# OpampTestBoard.net
KiCad netlist of a schematic drawn in EAGLE
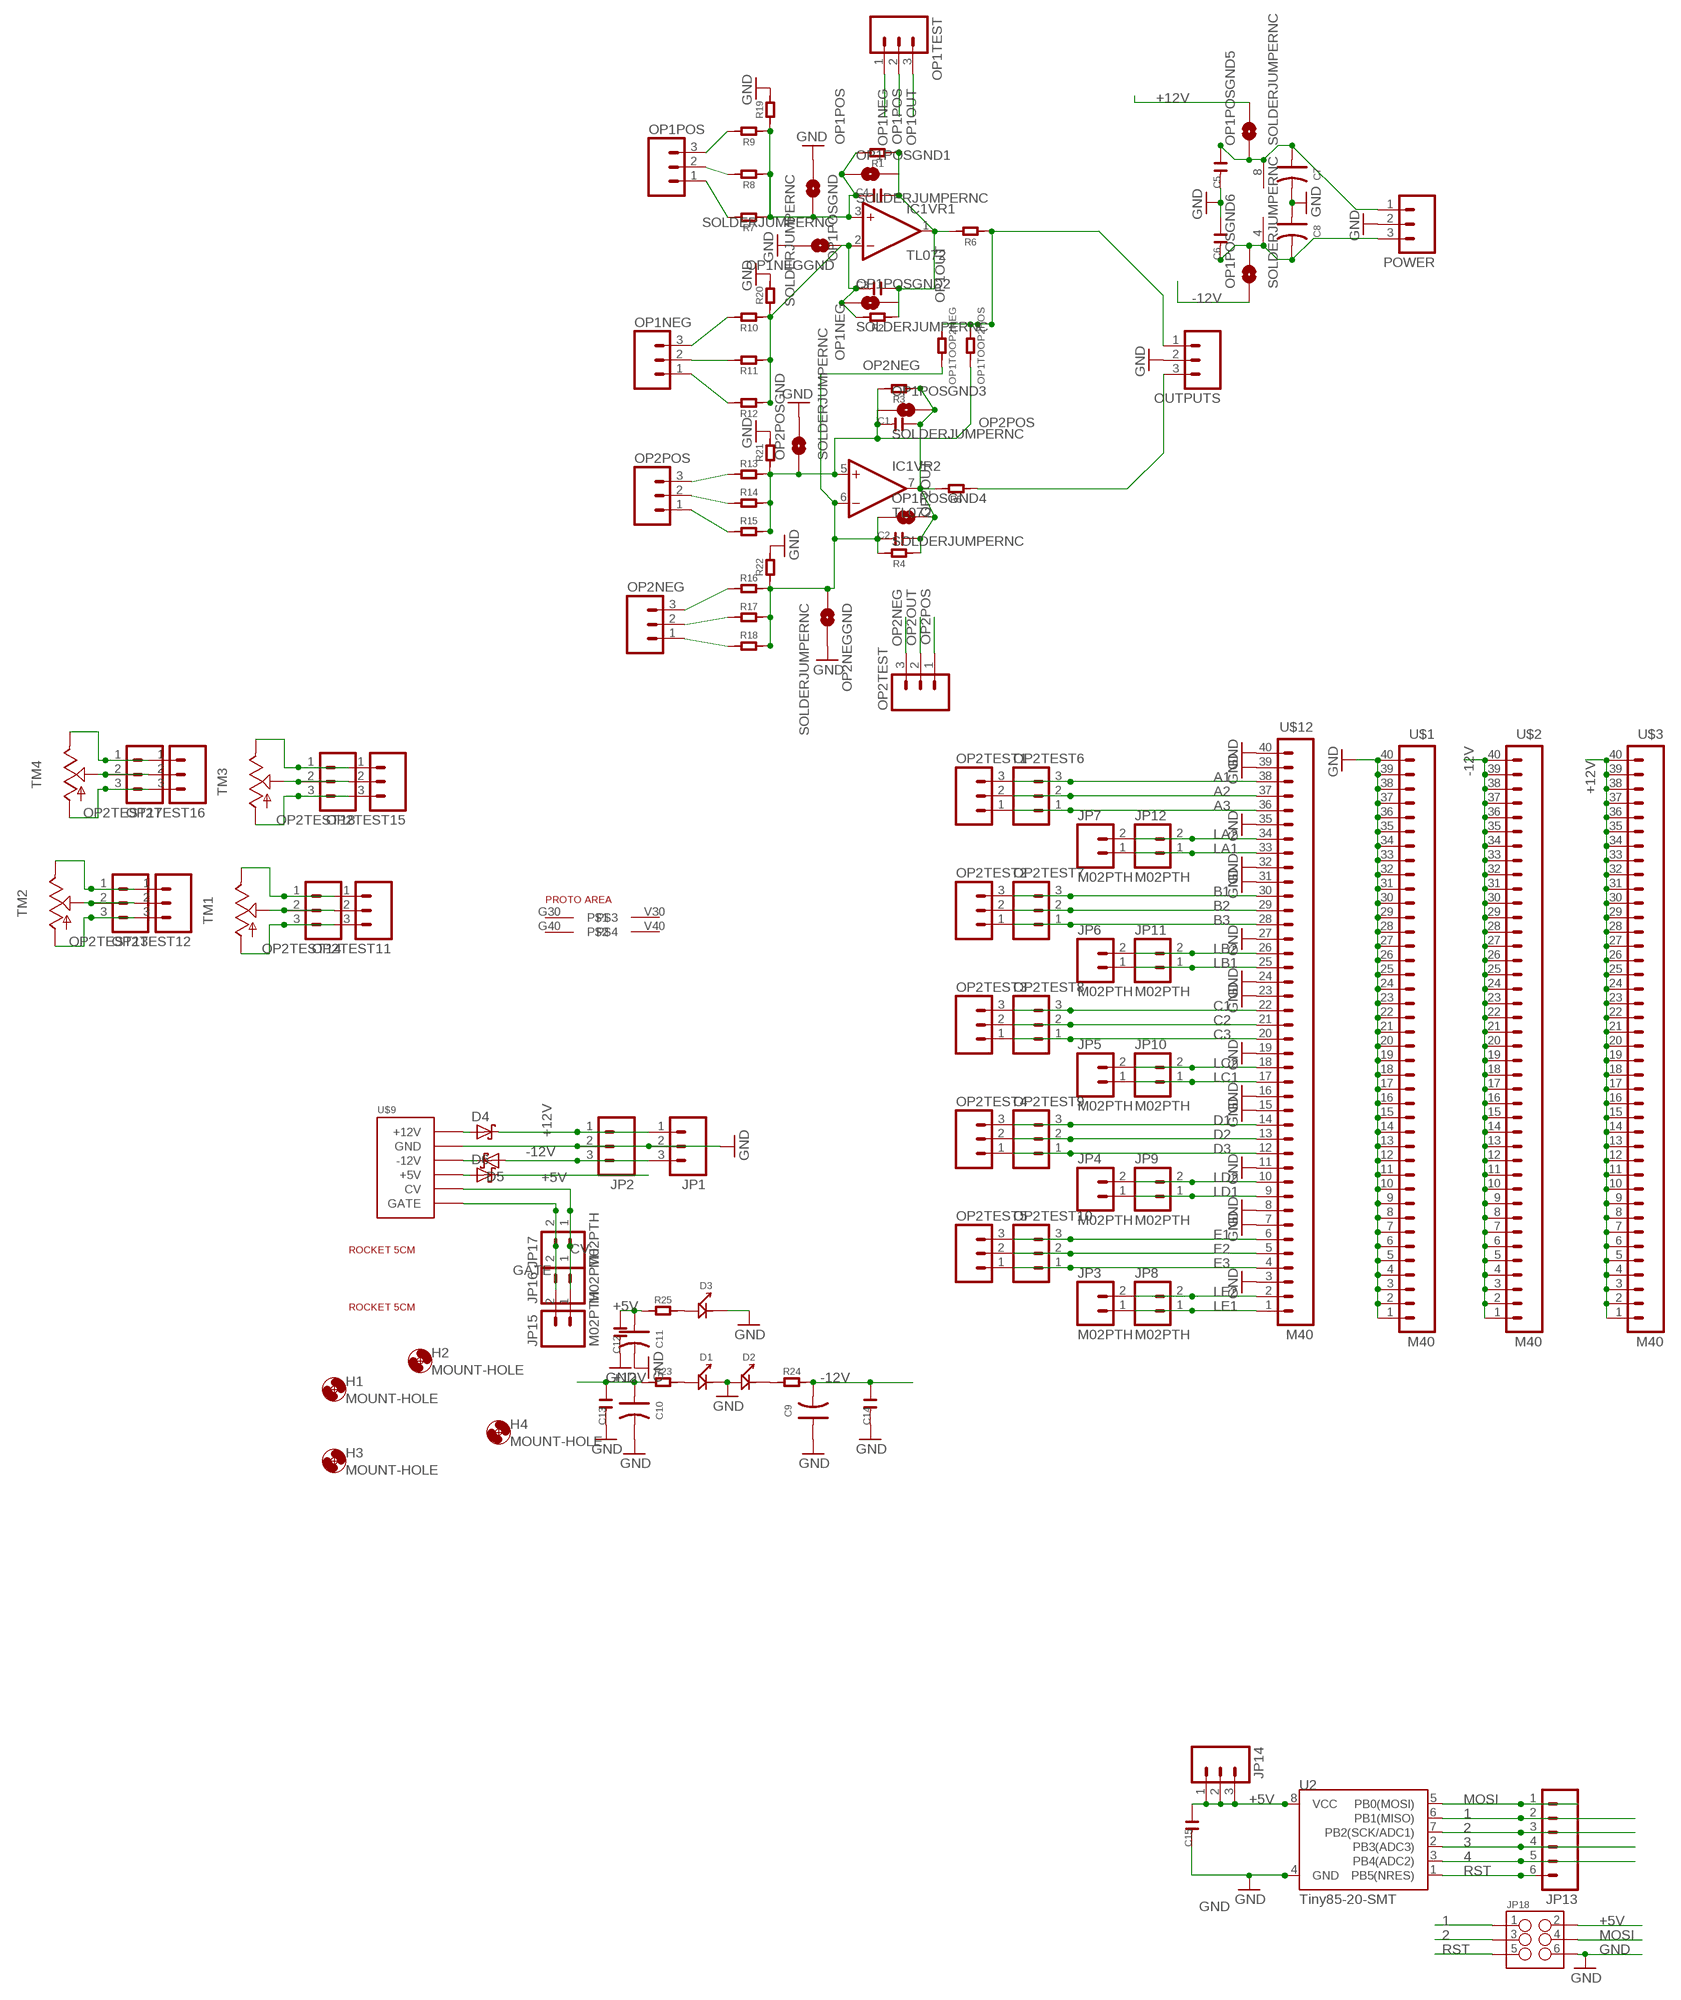
[diagram p0: schematic, sheet 1]

(export (version "E")
  (design (tool "Eeschema 10.0.6"))
  (components
    (comp (ref "C1")
      (value "C-0805")
      (footprint "eagle-import:C0805")
      (libsource (lib "eagle-import") (part "C-0805"))
    )
    (comp (ref "C2")
      (value "C-0805")
      (footprint "eagle-import:C0805")
      (libsource (lib "eagle-import") (part "C-0805"))
    )
    (comp (ref "C3")
      (value "C-0805")
      (footprint "eagle-import:C0805")
      (libsource (lib "eagle-import") (part "C-0805"))
    )
    (comp (ref "C4")
      (value "C-0805")
      (footprint "eagle-import:C0805")
      (libsource (lib "eagle-import") (part "C-0805"))
    )
    (comp (ref "C5")
      (value "C-0805")
      (footprint "eagle-import:C0805")
      (libsource (lib "eagle-import") (part "C-0805"))
    )
    (comp (ref "C6")
      (value "C-0805")
      (footprint "eagle-import:C0805")
      (libsource (lib "eagle-import") (part "C-0805"))
    )
    (comp (ref "C7")
      (value "C-POLAR-A")
      (footprint "eagle-import:AVX-A")
      (libsource (lib "eagle-import") (part "C-POLAR-A"))
    )
    (comp (ref "C8")
      (value "C-POLAR-A")
      (footprint "eagle-import:AVX-A")
      (libsource (lib "eagle-import") (part "C-POLAR-A"))
    )
    (comp (ref "C9")
      (value "C-POLAR-A")
      (footprint "eagle-import:AVX-A")
      (libsource (lib "eagle-import") (part "C-POLAR-A"))
    )
    (comp (ref "C10")
      (value "C-POLAR-A")
      (footprint "eagle-import:AVX-A")
      (libsource (lib "eagle-import") (part "C-POLAR-A"))
    )
    (comp (ref "C11")
      (value "C-POLAR-A")
      (footprint "eagle-import:AVX-A")
      (libsource (lib "eagle-import") (part "C-POLAR-A"))
    )
    (comp (ref "C12")
      (value "C-0805")
      (footprint "eagle-import:C0805")
      (libsource (lib "eagle-import") (part "C-0805"))
    )
    (comp (ref "C13")
      (value "C-0805")
      (footprint "eagle-import:C0805")
      (libsource (lib "eagle-import") (part "C-0805"))
    )
    (comp (ref "C14")
      (value "C-0805")
      (footprint "eagle-import:C0805")
      (libsource (lib "eagle-import") (part "C-0805"))
    )
    (comp (ref "C15")
      (value "C-0603")
      (footprint "eagle-import:C0603")
      (libsource (lib "eagle-import") (part "C-0603"))
    )
    (comp (ref "D1")
      (value "LED")
      (footprint "eagle-import:LED0603")
      (libsource (lib "eagle-import") (part "LED"))
    )
    (comp (ref "D2")
      (value "LED")
      (footprint "eagle-import:LED0603")
      (libsource (lib "eagle-import") (part "LED"))
    )
    (comp (ref "D3")
      (value "LED")
      (footprint "eagle-import:LED0603")
      (libsource (lib "eagle-import") (part "LED"))
    )
    (comp (ref "D4")
      (value "SCHOTTKY-DIODEDO41")
      (footprint "eagle-import:DO41-10")
      (libsource (lib "eagle-import") (part "SCHOTTKY-DIODEDO41"))
    )
    (comp (ref "D5")
      (value "SCHOTTKY-DIODEDO41")
      (footprint "eagle-import:DO41-10")
      (libsource (lib "eagle-import") (part "SCHOTTKY-DIODEDO41"))
    )
    (comp (ref "D6")
      (value "SCHOTTKY-DIODEDO41")
      (footprint "eagle-import:DO41-10")
      (libsource (lib "eagle-import") (part "SCHOTTKY-DIODEDO41"))
    )
    (comp (ref "H1")
      (value "MOUNT-HOLE")
      (footprint "eagle-import:3.2-NOMARKINGS-SMALLSAFEZONE")
      (libsource (lib "eagle-import") (part "MOUNT-HOLE"))
    )
    (comp (ref "H2")
      (value "MOUNT-HOLE")
      (footprint "eagle-import:3.2-NOMARKINGS-SMALLSAFEZONE")
      (libsource (lib "eagle-import") (part "MOUNT-HOLE"))
    )
    (comp (ref "H3")
      (value "MOUNT-HOLE")
      (footprint "eagle-import:3.2-NOMARKINGS-SMALLSAFEZONE")
      (libsource (lib "eagle-import") (part "MOUNT-HOLE"))
    )
    (comp (ref "H4")
      (value "MOUNT-HOLE")
      (footprint "eagle-import:3.2-NOMARKINGS-SMALLSAFEZONE")
      (libsource (lib "eagle-import") (part "MOUNT-HOLE"))
    )
    (comp (ref "IC1")
      (value "TL072")
      (footprint "eagle-import:SO08")
      (libsource (lib "eagle-import") (part "TL072"))
    )
    (comp (ref "JP1")
      (value "M03PTH")
      (footprint "eagle-import:1X03")
      (libsource (lib "eagle-import") (part "M03PTH"))
    )
    (comp (ref "JP2")
      (value "M03PTH")
      (footprint "eagle-import:1X03")
      (libsource (lib "eagle-import") (part "M03PTH"))
    )
    (comp (ref "JP3")
      (value "M02PTH")
      (footprint "eagle-import:1X02")
      (libsource (lib "eagle-import") (part "M02PTH"))
    )
    (comp (ref "JP4")
      (value "M02PTH")
      (footprint "eagle-import:1X02")
      (libsource (lib "eagle-import") (part "M02PTH"))
    )
    (comp (ref "JP5")
      (value "M02PTH")
      (footprint "eagle-import:1X02")
      (libsource (lib "eagle-import") (part "M02PTH"))
    )
    (comp (ref "JP6")
      (value "M02PTH")
      (footprint "eagle-import:1X02")
      (libsource (lib "eagle-import") (part "M02PTH"))
    )
    (comp (ref "JP7")
      (value "M02PTH")
      (footprint "eagle-import:1X02")
      (libsource (lib "eagle-import") (part "M02PTH"))
    )
    (comp (ref "JP8")
      (value "M02PTH")
      (footprint "eagle-import:1X02")
      (libsource (lib "eagle-import") (part "M02PTH"))
    )
    (comp (ref "JP9")
      (value "M02PTH")
      (footprint "eagle-import:1X02")
      (libsource (lib "eagle-import") (part "M02PTH"))
    )
    (comp (ref "JP10")
      (value "M02PTH")
      (footprint "eagle-import:1X02")
      (libsource (lib "eagle-import") (part "M02PTH"))
    )
    (comp (ref "JP11")
      (value "M02PTH")
      (footprint "eagle-import:1X02")
      (libsource (lib "eagle-import") (part "M02PTH"))
    )
    (comp (ref "JP12")
      (value "M02PTH")
      (footprint "eagle-import:1X02")
      (libsource (lib "eagle-import") (part "M02PTH"))
    )
    (comp (ref "JP13")
      (value "M06SIP")
      (footprint "eagle-import:1X06")
      (libsource (lib "eagle-import") (part "M06SIP"))
    )
    (comp (ref "JP14")
      (value "M03PTH")
      (footprint "eagle-import:1X03")
      (libsource (lib "eagle-import") (part "M03PTH"))
    )
    (comp (ref "JP15")
      (value "M02PTH")
      (footprint "eagle-import:1X02")
      (libsource (lib "eagle-import") (part "M02PTH"))
    )
    (comp (ref "JP16")
      (value "M02PTH")
      (footprint "eagle-import:1X02")
      (libsource (lib "eagle-import") (part "M02PTH"))
    )
    (comp (ref "JP17")
      (value "M02PTH")
      (footprint "eagle-import:1X02")
      (libsource (lib "eagle-import") (part "M02PTH"))
    )
    (comp (ref "JP18")
      (value "M03X2SMT")
      (footprint "eagle-import:2X3_SMT_POSTS")
      (libsource (lib "eagle-import") (part "M03X2SMT"))
    )
    (comp (ref "OP1NEG")
      (value "M03PTH")
      (footprint "eagle-import:1X03")
      (libsource (lib "eagle-import") (part "M03PTH"))
    )
    (comp (ref "OP1NEGGND")
      (value "SOLDERJUMPERNC")
      (footprint "eagle-import:SJ_2S")
      (libsource (lib "eagle-import") (part "SOLDERJUMPERNC"))
    )
    (comp (ref "OP1POS")
      (value "M03PTH")
      (footprint "eagle-import:1X03")
      (libsource (lib "eagle-import") (part "M03PTH"))
    )
    (comp (ref "OP1POSGND")
      (value "SOLDERJUMPERNC")
      (footprint "eagle-import:SJ_2S")
      (libsource (lib "eagle-import") (part "SOLDERJUMPERNC"))
    )
    (comp (ref "OP1POSGND1")
      (value "SOLDERJUMPERNC")
      (footprint "eagle-import:SJ_2S")
      (libsource (lib "eagle-import") (part "SOLDERJUMPERNC"))
    )
    (comp (ref "OP1POSGND2")
      (value "SOLDERJUMPERNC")
      (footprint "eagle-import:SJ_2S")
      (libsource (lib "eagle-import") (part "SOLDERJUMPERNC"))
    )
    (comp (ref "OP1POSGND3")
      (value "SOLDERJUMPERNC")
      (footprint "eagle-import:SJ_2S")
      (libsource (lib "eagle-import") (part "SOLDERJUMPERNC"))
    )
    (comp (ref "OP1POSGND4")
      (value "SOLDERJUMPERNC")
      (footprint "eagle-import:SJ_2S")
      (libsource (lib "eagle-import") (part "SOLDERJUMPERNC"))
    )
    (comp (ref "OP1POSGND5")
      (value "SOLDERJUMPERNC")
      (footprint "eagle-import:SJ_2S")
      (libsource (lib "eagle-import") (part "SOLDERJUMPERNC"))
    )
    (comp (ref "OP1POSGND6")
      (value "SOLDERJUMPERNC")
      (footprint "eagle-import:SJ_2S")
      (libsource (lib "eagle-import") (part "SOLDERJUMPERNC"))
    )
    (comp (ref "OP1TEST")
      (value "M03PTH")
      (footprint "eagle-import:1X03")
      (libsource (lib "eagle-import") (part "M03PTH"))
    )
    (comp (ref "OP1TOOP2NEG")
      (value "R-0603")
      (footprint "eagle-import:R0603")
      (libsource (lib "eagle-import") (part "R-0603"))
    )
    (comp (ref "OP1TOOP2POS")
      (value "R-0603")
      (footprint "eagle-import:R0603")
      (libsource (lib "eagle-import") (part "R-0603"))
    )
    (comp (ref "OP2NEG")
      (value "M03PTH")
      (footprint "eagle-import:1X03")
      (libsource (lib "eagle-import") (part "M03PTH"))
    )
    (comp (ref "OP2NEGGND")
      (value "SOLDERJUMPERNC")
      (footprint "eagle-import:SJ_2S")
      (libsource (lib "eagle-import") (part "SOLDERJUMPERNC"))
    )
    (comp (ref "OP2POS")
      (value "M03PTH")
      (footprint "eagle-import:1X03")
      (libsource (lib "eagle-import") (part "M03PTH"))
    )
    (comp (ref "OP2POSGND")
      (value "SOLDERJUMPERNC")
      (footprint "eagle-import:SJ_2S")
      (libsource (lib "eagle-import") (part "SOLDERJUMPERNC"))
    )
    (comp (ref "OP2TEST")
      (value "M03PTH")
      (footprint "eagle-import:1X03")
      (libsource (lib "eagle-import") (part "M03PTH"))
    )
    (comp (ref "OP2TEST1")
      (value "M03PTH")
      (footprint "eagle-import:1X03")
      (libsource (lib "eagle-import") (part "M03PTH"))
    )
    (comp (ref "OP2TEST2")
      (value "M03PTH")
      (footprint "eagle-import:1X03")
      (libsource (lib "eagle-import") (part "M03PTH"))
    )
    (comp (ref "OP2TEST3")
      (value "M03PTH")
      (footprint "eagle-import:1X03")
      (libsource (lib "eagle-import") (part "M03PTH"))
    )
    (comp (ref "OP2TEST4")
      (value "M03PTH")
      (footprint "eagle-import:1X03")
      (libsource (lib "eagle-import") (part "M03PTH"))
    )
    (comp (ref "OP2TEST5")
      (value "M03PTH")
      (footprint "eagle-import:1X03")
      (libsource (lib "eagle-import") (part "M03PTH"))
    )
    (comp (ref "OP2TEST6")
      (value "M03PTH")
      (footprint "eagle-import:1X03")
      (libsource (lib "eagle-import") (part "M03PTH"))
    )
    (comp (ref "OP2TEST7")
      (value "M03PTH")
      (footprint "eagle-import:1X03")
      (libsource (lib "eagle-import") (part "M03PTH"))
    )
    (comp (ref "OP2TEST8")
      (value "M03PTH")
      (footprint "eagle-import:1X03")
      (libsource (lib "eagle-import") (part "M03PTH"))
    )
    (comp (ref "OP2TEST9")
      (value "M03PTH")
      (footprint "eagle-import:1X03")
      (libsource (lib "eagle-import") (part "M03PTH"))
    )
    (comp (ref "OP2TEST10")
      (value "M03PTH")
      (footprint "eagle-import:1X03")
      (libsource (lib "eagle-import") (part "M03PTH"))
    )
    (comp (ref "OP2TEST11")
      (value "M03PTH")
      (footprint "eagle-import:1X03")
      (libsource (lib "eagle-import") (part "M03PTH"))
    )
    (comp (ref "OP2TEST12")
      (value "M03PTH")
      (footprint "eagle-import:1X03")
      (libsource (lib "eagle-import") (part "M03PTH"))
    )
    (comp (ref "OP2TEST13")
      (value "M03PTH")
      (footprint "eagle-import:1X03")
      (libsource (lib "eagle-import") (part "M03PTH"))
    )
    (comp (ref "OP2TEST14")
      (value "M03PTH")
      (footprint "eagle-import:1X03")
      (libsource (lib "eagle-import") (part "M03PTH"))
    )
    (comp (ref "OP2TEST15")
      (value "M03PTH")
      (footprint "eagle-import:1X03")
      (libsource (lib "eagle-import") (part "M03PTH"))
    )
    (comp (ref "OP2TEST16")
      (value "M03PTH")
      (footprint "eagle-import:1X03")
      (libsource (lib "eagle-import") (part "M03PTH"))
    )
    (comp (ref "OP2TEST17")
      (value "M03PTH")
      (footprint "eagle-import:1X03")
      (libsource (lib "eagle-import") (part "M03PTH"))
    )
    (comp (ref "OP2TEST18")
      (value "M03PTH")
      (footprint "eagle-import:1X03")
      (libsource (lib "eagle-import") (part "M03PTH"))
    )
    (comp (ref "OUTPUTS")
      (value "M03PTH")
      (footprint "eagle-import:1X03")
      (libsource (lib "eagle-import") (part "M03PTH"))
    )
    (comp (ref "POWER")
      (value "M03PTH")
      (footprint "eagle-import:1X03")
      (libsource (lib "eagle-import") (part "M03PTH"))
    )
    (comp (ref "R1")
      (value "R-0603")
      (footprint "eagle-import:R0603")
      (libsource (lib "eagle-import") (part "R-0603"))
    )
    (comp (ref "R2")
      (value "R-0603")
      (footprint "eagle-import:R0603")
      (libsource (lib "eagle-import") (part "R-0603"))
    )
    (comp (ref "R3")
      (value "R-0603")
      (footprint "eagle-import:R0603")
      (libsource (lib "eagle-import") (part "R-0603"))
    )
    (comp (ref "R4")
      (value "R-0603")
      (footprint "eagle-import:R0603")
      (libsource (lib "eagle-import") (part "R-0603"))
    )
    (comp (ref "R5")
      (value "R-0603")
      (footprint "eagle-import:R0603")
      (libsource (lib "eagle-import") (part "R-0603"))
    )
    (comp (ref "R6")
      (value "R-0603")
      (footprint "eagle-import:R0603")
      (libsource (lib "eagle-import") (part "R-0603"))
    )
    (comp (ref "R7")
      (value "R-0603")
      (footprint "eagle-import:R0603")
      (libsource (lib "eagle-import") (part "R-0603"))
    )
    (comp (ref "R8")
      (value "R-0603")
      (footprint "eagle-import:R0603")
      (libsource (lib "eagle-import") (part "R-0603"))
    )
    (comp (ref "R9")
      (value "R-0603")
      (footprint "eagle-import:R0603")
      (libsource (lib "eagle-import") (part "R-0603"))
    )
    (comp (ref "R10")
      (value "R-0603")
      (footprint "eagle-import:R0603")
      (libsource (lib "eagle-import") (part "R-0603"))
    )
    (comp (ref "R11")
      (value "R-0603")
      (footprint "eagle-import:R0603")
      (libsource (lib "eagle-import") (part "R-0603"))
    )
    (comp (ref "R12")
      (value "R-0603")
      (footprint "eagle-import:R0603")
      (libsource (lib "eagle-import") (part "R-0603"))
    )
    (comp (ref "R13")
      (value "R-0603")
      (footprint "eagle-import:R0603")
      (libsource (lib "eagle-import") (part "R-0603"))
    )
    (comp (ref "R14")
      (value "R-0603")
      (footprint "eagle-import:R0603")
      (libsource (lib "eagle-import") (part "R-0603"))
    )
    (comp (ref "R15")
      (value "R-0603")
      (footprint "eagle-import:R0603")
      (libsource (lib "eagle-import") (part "R-0603"))
    )
    (comp (ref "R16")
      (value "R-0603")
      (footprint "eagle-import:R0603")
      (libsource (lib "eagle-import") (part "R-0603"))
    )
    (comp (ref "R17")
      (value "R-0603")
      (footprint "eagle-import:R0603")
      (libsource (lib "eagle-import") (part "R-0603"))
    )
    (comp (ref "R18")
      (value "R-0603")
      (footprint "eagle-import:R0603")
      (libsource (lib "eagle-import") (part "R-0603"))
    )
    (comp (ref "R19")
      (value "R-0603")
      (footprint "eagle-import:R0603")
      (libsource (lib "eagle-import") (part "R-0603"))
    )
    (comp (ref "R20")
      (value "R-0603")
      (footprint "eagle-import:R0603")
      (libsource (lib "eagle-import") (part "R-0603"))
    )
    (comp (ref "R21")
      (value "R-0603")
      (footprint "eagle-import:R0603")
      (libsource (lib "eagle-import") (part "R-0603"))
    )
    (comp (ref "R22")
      (value "R-0603")
      (footprint "eagle-import:R0603")
      (libsource (lib "eagle-import") (part "R-0603"))
    )
    (comp (ref "R23")
      (value "R-0603")
      (footprint "eagle-import:R0603")
      (libsource (lib "eagle-import") (part "R-0603"))
    )
    (comp (ref "R24")
      (value "R-0603")
      (footprint "eagle-import:R0603")
      (libsource (lib "eagle-import") (part "R-0603"))
    )
    (comp (ref "R25")
      (value "R-0603")
      (footprint "eagle-import:R0603")
      (libsource (lib "eagle-import") (part "R-0603"))
    )
    (comp (ref "TM1")
      (value "TRIM")
      (footprint "eagle-import:6MM")
      (libsource (lib "eagle-import") (part "TRIM"))
    )
    (comp (ref "TM2")
      (value "TRIM")
      (footprint "eagle-import:6MM")
      (libsource (lib "eagle-import") (part "TRIM"))
    )
    (comp (ref "TM3")
      (value "TRIM")
      (footprint "eagle-import:6MM")
      (libsource (lib "eagle-import") (part "TRIM"))
    )
    (comp (ref "TM4")
      (value "TRIM")
      (footprint "eagle-import:6MM")
      (libsource (lib "eagle-import") (part "TRIM"))
    )
    (comp (ref "U$1")
      (value "M40")
      (footprint "eagle-import:1X40")
      (libsource (lib "eagle-import") (part "M40"))
    )
    (comp (ref "U$2")
      (value "M40")
      (footprint "eagle-import:1X40")
      (libsource (lib "eagle-import") (part "M40"))
    )
    (comp (ref "U$3")
      (value "M40")
      (footprint "eagle-import:1X40")
      (libsource (lib "eagle-import") (part "M40"))
    )
    (comp (ref "U$9")
      (value "POWER")
      (footprint "eagle-import:POWER_16")
      (libsource (lib "eagle-import") (part "POWER"))
    )
    (comp (ref "U$10")
      (value "ROCKET-5CM")
      (footprint "eagle-import:ROCKET-5CM")
      (libsource (lib "eagle-import") (part "ROCKET-5CM"))
    )
    (comp (ref "U$12")
      (value "M40")
      (footprint "eagle-import:1X40")
      (libsource (lib "eagle-import") (part "M40"))
    )
    (comp (ref "U$17")
      (value "ROCKET-5CM")
      (footprint "eagle-import:ROCKET-5CM")
      (libsource (lib "eagle-import") (part "ROCKET-5CM"))
    )
    (comp (ref "U$32")
      (value "PROTOAREA")
      (footprint "eagle-import:PROTO_10_24")
      (libsource (lib "eagle-import") (part "PROTOAREA"))
    )
    (comp (ref "U2")
      (value "Tiny85-20-SMT")
      (footprint "eagle-import:SO08-EIAJ")
      (libsource (lib "eagle-import") (part "ATTINY45TINY85-20-SMT"))
    )
  )
  (nets
    (net (code "1") (name "/+5V") (class "Default")
      (node (ref "C11") (pin "+") (pinfunction "1_+") (pintype "bidirectional"))
      (node (ref "C12") (pin "2") (pinfunction "2_2") (pintype "bidirectional"))
      (node (ref "C15") (pin "2") (pinfunction "2_2") (pintype "bidirectional"))
      (node (ref "D6") (pin "C") (pinfunction "C_C") (pintype "passive"))
      (node (ref "JP14") (pin "1") (pinfunction "1_1") (pintype "passive"))
      (node (ref "JP14") (pin "2") (pinfunction "2_2") (pintype "passive"))
      (node (ref "JP14") (pin "3") (pinfunction "3_3") (pintype "passive"))
      (node (ref "JP18") (pin "2") (pinfunction "2_2") (pintype "bidirectional"))
      (node (ref "R25") (pin "1") (pinfunction "1_1") (pintype "bidirectional"))
      (node (ref "U2") (pin "8") (pinfunction "VCC_8") (pintype "bidirectional"))
    )
    (net (code "2") (name "/+12V") (class "Default")
      (node (ref "C10") (pin "+") (pinfunction "1_+") (pintype "bidirectional"))
      (node (ref "C13") (pin "2") (pinfunction "2_2") (pintype "bidirectional"))
      (node (ref "D4") (pin "C") (pinfunction "C_C") (pintype "passive"))
      (node (ref "JP1") (pin "1") (pinfunction "1_1") (pintype "passive"))
      (node (ref "JP2") (pin "1") (pinfunction "1_1") (pintype "passive"))
      (node (ref "OP1POSGND5") (pin "2") (pinfunction "2_2") (pintype "passive"))
      (node (ref "R23") (pin "1") (pinfunction "1_1") (pintype "bidirectional"))
      (node (ref "U$3") (pin "1") (pinfunction "1_1") (pintype "passive"))
      (node (ref "U$3") (pin "10") (pinfunction "10_10") (pintype "passive"))
      (node (ref "U$3") (pin "11") (pinfunction "11_11") (pintype "passive"))
      (node (ref "U$3") (pin "12") (pinfunction "12_12") (pintype "passive"))
      (node (ref "U$3") (pin "13") (pinfunction "13_13") (pintype "passive"))
      (node (ref "U$3") (pin "14") (pinfunction "14_14") (pintype "passive"))
      (node (ref "U$3") (pin "15") (pinfunction "15_15") (pintype "passive"))
      (node (ref "U$3") (pin "16") (pinfunction "16_16") (pintype "passive"))
      (node (ref "U$3") (pin "17") (pinfunction "17_17") (pintype "passive"))
      (node (ref "U$3") (pin "18") (pinfunction "18_18") (pintype "passive"))
      (node (ref "U$3") (pin "19") (pinfunction "19_19") (pintype "passive"))
      (node (ref "U$3") (pin "2") (pinfunction "2_2") (pintype "passive"))
      (node (ref "U$3") (pin "20") (pinfunction "20_20") (pintype "passive"))
      (node (ref "U$3") (pin "21") (pinfunction "21_21") (pintype "passive"))
      (node (ref "U$3") (pin "22") (pinfunction "22_22") (pintype "passive"))
      (node (ref "U$3") (pin "23") (pinfunction "23_23") (pintype "passive"))
      (node (ref "U$3") (pin "24") (pinfunction "24_24") (pintype "passive"))
      (node (ref "U$3") (pin "25") (pinfunction "25_25") (pintype "passive"))
      (node (ref "U$3") (pin "26") (pinfunction "26_26") (pintype "passive"))
      (node (ref "U$3") (pin "27") (pinfunction "27_27") (pintype "passive"))
      (node (ref "U$3") (pin "28") (pinfunction "28_28") (pintype "passive"))
      (node (ref "U$3") (pin "29") (pinfunction "29_29") (pintype "passive"))
      (node (ref "U$3") (pin "3") (pinfunction "3_3") (pintype "passive"))
      (node (ref "U$3") (pin "30") (pinfunction "30_30") (pintype "passive"))
      (node (ref "U$3") (pin "31") (pinfunction "31_31") (pintype "passive"))
      (node (ref "U$3") (pin "32") (pinfunction "32_32") (pintype "passive"))
      (node (ref "U$3") (pin "33") (pinfunction "33_33") (pintype "passive"))
      (node (ref "U$3") (pin "34") (pinfunction "34_34") (pintype "passive"))
      (node (ref "U$3") (pin "35") (pinfunction "35_35") (pintype "passive"))
      (node (ref "U$3") (pin "36") (pinfunction "36_36") (pintype "passive"))
      (node (ref "U$3") (pin "37") (pinfunction "37_37") (pintype "passive"))
      (node (ref "U$3") (pin "38") (pinfunction "38_38") (pintype "passive"))
      (node (ref "U$3") (pin "39") (pinfunction "39_39") (pintype "passive"))
      (node (ref "U$3") (pin "4") (pinfunction "4_4") (pintype "passive"))
      (node (ref "U$3") (pin "40") (pinfunction "40_40") (pintype "passive"))
      (node (ref "U$3") (pin "5") (pinfunction "5_5") (pintype "passive"))
      (node (ref "U$3") (pin "6") (pinfunction "6_6") (pintype "passive"))
      (node (ref "U$3") (pin "7") (pinfunction "7_7") (pintype "passive"))
      (node (ref "U$3") (pin "8") (pinfunction "8_8") (pintype "passive"))
      (node (ref "U$3") (pin "9") (pinfunction "9_9") (pintype "passive"))
    )
    (net (code "3") (name "/-12V") (class "Default")
      (node (ref "C14") (pin "2") (pinfunction "2_2") (pintype "bidirectional"))
      (node (ref "C9") (pin "-") (pinfunction "2_-") (pintype "bidirectional"))
      (node (ref "D5") (pin "A") (pinfunction "A_A") (pintype "passive"))
      (node (ref "JP1") (pin "3") (pinfunction "3_3") (pintype "passive"))
      (node (ref "JP2") (pin "3") (pinfunction "3_3") (pintype "passive"))
      (node (ref "OP1POSGND6") (pin "1") (pinfunction "1_1") (pintype "passive"))
      (node (ref "R24") (pin "2") (pinfunction "2_2") (pintype "bidirectional"))
      (node (ref "U$2") (pin "1") (pinfunction "1_1") (pintype "passive"))
      (node (ref "U$2") (pin "10") (pinfunction "10_10") (pintype "passive"))
      (node (ref "U$2") (pin "11") (pinfunction "11_11") (pintype "passive"))
      (node (ref "U$2") (pin "12") (pinfunction "12_12") (pintype "passive"))
      (node (ref "U$2") (pin "13") (pinfunction "13_13") (pintype "passive"))
      (node (ref "U$2") (pin "14") (pinfunction "14_14") (pintype "passive"))
      (node (ref "U$2") (pin "15") (pinfunction "15_15") (pintype "passive"))
      (node (ref "U$2") (pin "16") (pinfunction "16_16") (pintype "passive"))
      (node (ref "U$2") (pin "17") (pinfunction "17_17") (pintype "passive"))
      (node (ref "U$2") (pin "18") (pinfunction "18_18") (pintype "passive"))
      (node (ref "U$2") (pin "19") (pinfunction "19_19") (pintype "passive"))
      (node (ref "U$2") (pin "2") (pinfunction "2_2") (pintype "passive"))
      (node (ref "U$2") (pin "20") (pinfunction "20_20") (pintype "passive"))
      (node (ref "U$2") (pin "21") (pinfunction "21_21") (pintype "passive"))
      (node (ref "U$2") (pin "22") (pinfunction "22_22") (pintype "passive"))
      (node (ref "U$2") (pin "23") (pinfunction "23_23") (pintype "passive"))
      (node (ref "U$2") (pin "24") (pinfunction "24_24") (pintype "passive"))
      (node (ref "U$2") (pin "25") (pinfunction "25_25") (pintype "passive"))
      (node (ref "U$2") (pin "26") (pinfunction "26_26") (pintype "passive"))
      (node (ref "U$2") (pin "27") (pinfunction "27_27") (pintype "passive"))
      (node (ref "U$2") (pin "28") (pinfunction "28_28") (pintype "passive"))
      (node (ref "U$2") (pin "29") (pinfunction "29_29") (pintype "passive"))
      (node (ref "U$2") (pin "3") (pinfunction "3_3") (pintype "passive"))
      (node (ref "U$2") (pin "30") (pinfunction "30_30") (pintype "passive"))
      (node (ref "U$2") (pin "31") (pinfunction "31_31") (pintype "passive"))
      (node (ref "U$2") (pin "32") (pinfunction "32_32") (pintype "passive"))
      (node (ref "U$2") (pin "33") (pinfunction "33_33") (pintype "passive"))
      (node (ref "U$2") (pin "34") (pinfunction "34_34") (pintype "passive"))
      (node (ref "U$2") (pin "35") (pinfunction "35_35") (pintype "passive"))
      (node (ref "U$2") (pin "36") (pinfunction "36_36") (pintype "passive"))
      (node (ref "U$2") (pin "37") (pinfunction "37_37") (pintype "passive"))
      (node (ref "U$2") (pin "38") (pinfunction "38_38") (pintype "passive"))
      (node (ref "U$2") (pin "39") (pinfunction "39_39") (pintype "passive"))
      (node (ref "U$2") (pin "4") (pinfunction "4_4") (pintype "passive"))
      (node (ref "U$2") (pin "40") (pinfunction "40_40") (pintype "passive"))
      (node (ref "U$2") (pin "5") (pinfunction "5_5") (pintype "passive"))
      (node (ref "U$2") (pin "6") (pinfunction "6_6") (pintype "passive"))
      (node (ref "U$2") (pin "7") (pinfunction "7_7") (pintype "passive"))
      (node (ref "U$2") (pin "8") (pinfunction "8_8") (pintype "passive"))
      (node (ref "U$2") (pin "9") (pinfunction "9_9") (pintype "passive"))
    )
    (net (code "4") (name "/1") (class "Default")
      (node (ref "JP13") (pin "2") (pinfunction "2_2") (pintype "passive"))
      (node (ref "JP18") (pin "1") (pinfunction "1_1") (pintype "bidirectional"))
      (node (ref "U2") (pin "6") (pinfunction "PB1(MISO)_6") (pintype "bidirectional"))
    )
    (net (code "5") (name "/2") (class "Default")
      (node (ref "JP13") (pin "3") (pinfunction "3_3") (pintype "passive"))
      (node (ref "JP18") (pin "3") (pinfunction "3_3") (pintype "bidirectional"))
      (node (ref "U2") (pin "7") (pinfunction "PB2(SCK/ADC1)_7") (pintype "bidirectional"))
    )
    (net (code "6") (name "/3") (class "Default")
      (node (ref "JP13") (pin "4") (pinfunction "4_4") (pintype "passive"))
      (node (ref "U2") (pin "2") (pinfunction "PB3(ADC3)_2") (pintype "bidirectional"))
    )
    (net (code "7") (name "/4") (class "Default")
      (node (ref "JP13") (pin "5") (pinfunction "5_5") (pintype "passive"))
      (node (ref "U2") (pin "3") (pinfunction "PB4(ADC2)_3") (pintype "bidirectional"))
    )
    (net (code "8") (name "/A1") (class "Default")
      (node (ref "OP2TEST1") (pin "3") (pinfunction "3_3") (pintype "passive"))
      (node (ref "OP2TEST6") (pin "3") (pinfunction "3_3") (pintype "passive"))
      (node (ref "U$12") (pin "38") (pinfunction "38_38") (pintype "passive"))
    )
    (net (code "9") (name "/A2") (class "Default")
      (node (ref "OP2TEST1") (pin "2") (pinfunction "2_2") (pintype "passive"))
      (node (ref "OP2TEST6") (pin "2") (pinfunction "2_2") (pintype "passive"))
      (node (ref "U$12") (pin "37") (pinfunction "37_37") (pintype "passive"))
    )
    (net (code "10") (name "/A3") (class "Default")
      (node (ref "OP2TEST1") (pin "1") (pinfunction "1_1") (pintype "passive"))
      (node (ref "OP2TEST6") (pin "1") (pinfunction "1_1") (pintype "passive"))
      (node (ref "U$12") (pin "36") (pinfunction "36_36") (pintype "passive"))
    )
    (net (code "11") (name "/B1") (class "Default")
      (node (ref "OP2TEST2") (pin "3") (pinfunction "3_3") (pintype "passive"))
      (node (ref "OP2TEST7") (pin "3") (pinfunction "3_3") (pintype "passive"))
      (node (ref "U$12") (pin "30") (pinfunction "30_30") (pintype "passive"))
    )
    (net (code "12") (name "/B2") (class "Default")
      (node (ref "OP2TEST2") (pin "2") (pinfunction "2_2") (pintype "passive"))
      (node (ref "OP2TEST7") (pin "2") (pinfunction "2_2") (pintype "passive"))
      (node (ref "U$12") (pin "29") (pinfunction "29_29") (pintype "passive"))
    )
    (net (code "13") (name "/B3") (class "Default")
      (node (ref "OP2TEST2") (pin "1") (pinfunction "1_1") (pintype "passive"))
      (node (ref "OP2TEST7") (pin "1") (pinfunction "1_1") (pintype "passive"))
      (node (ref "U$12") (pin "28") (pinfunction "28_28") (pintype "passive"))
    )
    (net (code "14") (name "/C1") (class "Default")
      (node (ref "OP2TEST3") (pin "3") (pinfunction "3_3") (pintype "passive"))
      (node (ref "OP2TEST8") (pin "3") (pinfunction "3_3") (pintype "passive"))
      (node (ref "U$12") (pin "22") (pinfunction "22_22") (pintype "passive"))
    )
    (net (code "15") (name "/C2") (class "Default")
      (node (ref "OP2TEST3") (pin "2") (pinfunction "2_2") (pintype "passive"))
      (node (ref "OP2TEST8") (pin "2") (pinfunction "2_2") (pintype "passive"))
      (node (ref "U$12") (pin "21") (pinfunction "21_21") (pintype "passive"))
    )
    (net (code "16") (name "/C3") (class "Default")
      (node (ref "OP2TEST3") (pin "1") (pinfunction "1_1") (pintype "passive"))
      (node (ref "OP2TEST8") (pin "1") (pinfunction "1_1") (pintype "passive"))
      (node (ref "U$12") (pin "20") (pinfunction "20_20") (pintype "passive"))
    )
    (net (code "17") (name "/CV") (class "Default")
      (node (ref "JP15") (pin "1") (pinfunction "1_1") (pintype "passive"))
      (node (ref "JP16") (pin "1") (pinfunction "1_1") (pintype "passive"))
      (node (ref "JP17") (pin "1") (pinfunction "1_1") (pintype "passive"))
      (node (ref "U$9") (pin "13") (pinfunction "CV_13") (pintype "bidirectional"))
      (node (ref "U$9") (pin "14") (pinfunction "CV_14") (pintype "bidirectional"))
    )
    (net (code "18") (name "/D1") (class "Default")
      (node (ref "OP2TEST4") (pin "3") (pinfunction "3_3") (pintype "passive"))
      (node (ref "OP2TEST9") (pin "3") (pinfunction "3_3") (pintype "passive"))
      (node (ref "U$12") (pin "14") (pinfunction "14_14") (pintype "passive"))
    )
    (net (code "19") (name "/D2") (class "Default")
      (node (ref "OP2TEST4") (pin "2") (pinfunction "2_2") (pintype "passive"))
      (node (ref "OP2TEST9") (pin "2") (pinfunction "2_2") (pintype "passive"))
      (node (ref "U$12") (pin "13") (pinfunction "13_13") (pintype "passive"))
    )
    (net (code "20") (name "/D3") (class "Default")
      (node (ref "OP2TEST4") (pin "1") (pinfunction "1_1") (pintype "passive"))
      (node (ref "OP2TEST9") (pin "1") (pinfunction "1_1") (pintype "passive"))
      (node (ref "U$12") (pin "12") (pinfunction "12_12") (pintype "passive"))
    )
    (net (code "21") (name "/E1") (class "Default")
      (node (ref "OP2TEST10") (pin "3") (pinfunction "3_3") (pintype "passive"))
      (node (ref "OP2TEST5") (pin "3") (pinfunction "3_3") (pintype "passive"))
      (node (ref "U$12") (pin "6") (pinfunction "6_6") (pintype "passive"))
    )
    (net (code "22") (name "/E2") (class "Default")
      (node (ref "OP2TEST10") (pin "2") (pinfunction "2_2") (pintype "passive"))
      (node (ref "OP2TEST5") (pin "2") (pinfunction "2_2") (pintype "passive"))
      (node (ref "U$12") (pin "5") (pinfunction "5_5") (pintype "passive"))
    )
    (net (code "23") (name "/E3") (class "Default")
      (node (ref "OP2TEST10") (pin "1") (pinfunction "1_1") (pintype "passive"))
      (node (ref "OP2TEST5") (pin "1") (pinfunction "1_1") (pintype "passive"))
      (node (ref "U$12") (pin "4") (pinfunction "4_4") (pintype "passive"))
    )
    (net (code "24") (name "/GATE") (class "Default")
      (node (ref "JP15") (pin "2") (pinfunction "2_2") (pintype "passive"))
      (node (ref "JP16") (pin "2") (pinfunction "2_2") (pintype "passive"))
      (node (ref "JP17") (pin "2") (pinfunction "2_2") (pintype "passive"))
      (node (ref "U$9") (pin "15") (pinfunction "GATE_15") (pintype "bidirectional"))
      (node (ref "U$9") (pin "16") (pinfunction "GATE_16") (pintype "bidirectional"))
    )
    (net (code "25") (name "/LA1") (class "Default")
      (node (ref "JP12") (pin "1") (pinfunction "1_1") (pintype "passive"))
      (node (ref "JP7") (pin "1") (pinfunction "1_1") (pintype "passive"))
      (node (ref "U$12") (pin "33") (pinfunction "33_33") (pintype "passive"))
    )
    (net (code "26") (name "/LA2") (class "Default")
      (node (ref "JP12") (pin "2") (pinfunction "2_2") (pintype "passive"))
      (node (ref "JP7") (pin "2") (pinfunction "2_2") (pintype "passive"))
      (node (ref "U$12") (pin "34") (pinfunction "34_34") (pintype "passive"))
    )
    (net (code "27") (name "/LB1") (class "Default")
      (node (ref "JP11") (pin "1") (pinfunction "1_1") (pintype "passive"))
      (node (ref "JP6") (pin "1") (pinfunction "1_1") (pintype "passive"))
      (node (ref "U$12") (pin "25") (pinfunction "25_25") (pintype "passive"))
    )
    (net (code "28") (name "/LB2") (class "Default")
      (node (ref "JP11") (pin "2") (pinfunction "2_2") (pintype "passive"))
      (node (ref "JP6") (pin "2") (pinfunction "2_2") (pintype "passive"))
      (node (ref "U$12") (pin "26") (pinfunction "26_26") (pintype "passive"))
    )
    (net (code "29") (name "/LC1") (class "Default")
      (node (ref "JP10") (pin "1") (pinfunction "1_1") (pintype "passive"))
      (node (ref "JP5") (pin "1") (pinfunction "1_1") (pintype "passive"))
      (node (ref "U$12") (pin "17") (pinfunction "17_17") (pintype "passive"))
    )
    (net (code "30") (name "/LC2") (class "Default")
      (node (ref "JP10") (pin "2") (pinfunction "2_2") (pintype "passive"))
      (node (ref "JP5") (pin "2") (pinfunction "2_2") (pintype "passive"))
      (node (ref "U$12") (pin "18") (pinfunction "18_18") (pintype "passive"))
    )
    (net (code "31") (name "/LD1") (class "Default")
      (node (ref "JP4") (pin "1") (pinfunction "1_1") (pintype "passive"))
      (node (ref "JP9") (pin "1") (pinfunction "1_1") (pintype "passive"))
      (node (ref "U$12") (pin "9") (pinfunction "9_9") (pintype "passive"))
    )
    (net (code "32") (name "/LD2") (class "Default")
      (node (ref "JP4") (pin "2") (pinfunction "2_2") (pintype "passive"))
      (node (ref "JP9") (pin "2") (pinfunction "2_2") (pintype "passive"))
      (node (ref "U$12") (pin "10") (pinfunction "10_10") (pintype "passive"))
    )
    (net (code "33") (name "/LE1") (class "Default")
      (node (ref "JP3") (pin "1") (pinfunction "1_1") (pintype "passive"))
      (node (ref "JP8") (pin "1") (pinfunction "1_1") (pintype "passive"))
      (node (ref "U$12") (pin "1") (pinfunction "1_1") (pintype "passive"))
    )
    (net (code "34") (name "/LE2") (class "Default")
      (node (ref "JP3") (pin "2") (pinfunction "2_2") (pintype "passive"))
      (node (ref "JP8") (pin "2") (pinfunction "2_2") (pintype "passive"))
      (node (ref "U$12") (pin "2") (pinfunction "2_2") (pintype "passive"))
    )
    (net (code "35") (name "/MOSI") (class "Default")
      (node (ref "JP13") (pin "1") (pinfunction "1_1") (pintype "passive"))
      (node (ref "JP18") (pin "4") (pinfunction "4_4") (pintype "bidirectional"))
      (node (ref "U2") (pin "5") (pinfunction "PB0(MOSI)_5") (pintype "bidirectional"))
    )
    (net (code "36") (name "/OP1NEG") (class "Default")
      (node (ref "C3") (pin "1") (pinfunction "1_1") (pintype "bidirectional"))
      (node (ref "IC1") (pin "2") (pinfunction "-IN_2") (pintype "input"))
      (node (ref "OP1NEGGND") (pin "1") (pinfunction "1_1") (pintype "passive"))
      (node (ref "OP1POSGND2") (pin "1") (pinfunction "1_1") (pintype "passive"))
      (node (ref "OP1TEST") (pin "1") (pinfunction "1_1") (pintype "passive"))
      (node (ref "R10") (pin "1") (pinfunction "1_1") (pintype "bidirectional"))
      (node (ref "R11") (pin "1") (pinfunction "1_1") (pintype "bidirectional"))
      (node (ref "R12") (pin "1") (pinfunction "1_1") (pintype "bidirectional"))
      (node (ref "R2") (pin "2") (pinfunction "2_2") (pintype "bidirectional"))
      (node (ref "R20") (pin "1") (pinfunction "1_1") (pintype "bidirectional"))
    )
    (net (code "37") (name "/OP1OUT") (class "Default")
      (node (ref "C3") (pin "2") (pinfunction "2_2") (pintype "bidirectional"))
      (node (ref "C4") (pin "2") (pinfunction "2_2") (pintype "bidirectional"))
      (node (ref "IC1") (pin "1") (pinfunction "OUT_1") (pintype "output"))
      (node (ref "OP1POSGND1") (pin "2") (pinfunction "2_2") (pintype "passive"))
      (node (ref "OP1POSGND2") (pin "2") (pinfunction "2_2") (pintype "passive"))
      (node (ref "OP1TEST") (pin "3") (pinfunction "3_3") (pintype "passive"))
      (node (ref "R1") (pin "1") (pinfunction "1_1") (pintype "bidirectional"))
      (node (ref "R2") (pin "1") (pinfunction "1_1") (pintype "bidirectional"))
      (node (ref "R6") (pin "2") (pinfunction "2_2") (pintype "bidirectional"))
    )
    (net (code "38") (name "/OP1POS") (class "Default")
      (node (ref "C4") (pin "1") (pinfunction "1_1") (pintype "bidirectional"))
      (node (ref "IC1") (pin "3") (pinfunction "+IN_3") (pintype "input"))
      (node (ref "OP1POSGND") (pin "2") (pinfunction "2_2") (pintype "passive"))
      (node (ref "OP1POSGND1") (pin "1") (pinfunction "1_1") (pintype "passive"))
      (node (ref "OP1TEST") (pin "2") (pinfunction "2_2") (pintype "passive"))
      (node (ref "R1") (pin "2") (pinfunction "2_2") (pintype "bidirectional"))
      (node (ref "R19") (pin "1") (pinfunction "1_1") (pintype "bidirectional"))
      (node (ref "R7") (pin "1") (pinfunction "1_1") (pintype "bidirectional"))
      (node (ref "R8") (pin "1") (pinfunction "1_1") (pintype "bidirectional"))
      (node (ref "R9") (pin "1") (pinfunction "1_1") (pintype "bidirectional"))
    )
    (net (code "39") (name "/OP2NEG") (class "Default")
      (node (ref "C2") (pin "1") (pinfunction "1_1") (pintype "bidirectional"))
      (node (ref "IC1") (pin "6") (pinfunction "-IN_6") (pintype "input"))
      (node (ref "OP1POSGND4") (pin "1") (pinfunction "1_1") (pintype "passive"))
      (node (ref "OP1TOOP2NEG") (pin "2") (pinfunction "2_2") (pintype "bidirectional"))
      (node (ref "OP2NEGGND") (pin "1") (pinfunction "1_1") (pintype "passive"))
      (node (ref "OP2TEST") (pin "3") (pinfunction "3_3") (pintype "passive"))
      (node (ref "R16") (pin "2") (pinfunction "2_2") (pintype "bidirectional"))
      (node (ref "R17") (pin "2") (pinfunction "2_2") (pintype "bidirectional"))
      (node (ref "R18") (pin "2") (pinfunction "2_2") (pintype "bidirectional"))
      (node (ref "R22") (pin "1") (pinfunction "1_1") (pintype "bidirectional"))
      (node (ref "R4") (pin "2") (pinfunction "2_2") (pintype "bidirectional"))
    )
    (net (code "40") (name "/OP2OUT") (class "Default")
      (node (ref "C1") (pin "2") (pinfunction "2_2") (pintype "bidirectional"))
      (node (ref "C2") (pin "2") (pinfunction "2_2") (pintype "bidirectional"))
      (node (ref "IC1") (pin "7") (pinfunction "OUT_7") (pintype "output"))
      (node (ref "OP1POSGND3") (pin "2") (pinfunction "2_2") (pintype "passive"))
      (node (ref "OP1POSGND4") (pin "2") (pinfunction "2_2") (pintype "passive"))
      (node (ref "OP2TEST") (pin "2") (pinfunction "2_2") (pintype "passive"))
      (node (ref "R3") (pin "1") (pinfunction "1_1") (pintype "bidirectional"))
      (node (ref "R4") (pin "1") (pinfunction "1_1") (pintype "bidirectional"))
      (node (ref "R5") (pin "2") (pinfunction "2_2") (pintype "bidirectional"))
    )
    (net (code "41") (name "/OP2POS") (class "Default")
      (node (ref "C1") (pin "1") (pinfunction "1_1") (pintype "bidirectional"))
      (node (ref "IC1") (pin "5") (pinfunction "+IN_5") (pintype "input"))
      (node (ref "OP1POSGND3") (pin "1") (pinfunction "1_1") (pintype "passive"))
      (node (ref "OP1TOOP2POS") (pin "2") (pinfunction "2_2") (pintype "bidirectional"))
      (node (ref "OP2POSGND") (pin "1") (pinfunction "1_1") (pintype "passive"))
      (node (ref "OP2TEST") (pin "1") (pinfunction "1_1") (pintype "passive"))
      (node (ref "R13") (pin "2") (pinfunction "2_2") (pintype "bidirectional"))
      (node (ref "R14") (pin "2") (pinfunction "2_2") (pintype "bidirectional"))
      (node (ref "R15") (pin "2") (pinfunction "2_2") (pintype "bidirectional"))
      (node (ref "R21") (pin "1") (pinfunction "1_1") (pintype "bidirectional"))
      (node (ref "R3") (pin "2") (pinfunction "2_2") (pintype "bidirectional"))
    )
    (net (code "42") (name "/RST") (class "Default")
      (node (ref "JP13") (pin "6") (pinfunction "6_6") (pintype "passive"))
      (node (ref "JP18") (pin "5") (pinfunction "5_5") (pintype "bidirectional"))
      (node (ref "U2") (pin "1") (pinfunction "PB5(NRES)_1") (pintype "bidirectional"))
    )
    (net (code "43") (name "GND") (class "Default")
      (node (ref "C10") (pin "-") (pinfunction "2_-") (pintype "bidirectional"))
      (node (ref "C11") (pin "-") (pinfunction "2_-") (pintype "bidirectional"))
      (node (ref "C12") (pin "1") (pinfunction "1_1") (pintype "bidirectional"))
      (node (ref "C13") (pin "1") (pinfunction "1_1") (pintype "bidirectional"))
      (node (ref "C14") (pin "1") (pinfunction "1_1") (pintype "bidirectional"))
      (node (ref "C15") (pin "1") (pinfunction "1_1") (pintype "bidirectional"))
      (node (ref "C5") (pin "1") (pinfunction "1_1") (pintype "bidirectional"))
      (node (ref "C6") (pin "2") (pinfunction "2_2") (pintype "bidirectional"))
      (node (ref "C7") (pin "-") (pinfunction "2_-") (pintype "bidirectional"))
      (node (ref "C8") (pin "+") (pinfunction "1_+") (pintype "bidirectional"))
      (node (ref "C9") (pin "+") (pinfunction "1_+") (pintype "bidirectional"))
      (node (ref "D1") (pin "-") (pinfunction "-_-") (pintype "passive"))
      (node (ref "D2") (pin "+") (pinfunction "+_+") (pintype "passive"))
      (node (ref "D3") (pin "-") (pinfunction "-_-") (pintype "passive"))
      (node (ref "JP1") (pin "2") (pinfunction "2_2") (pintype "passive"))
      (node (ref "JP18") (pin "6") (pinfunction "6_6") (pintype "bidirectional"))
      (node (ref "JP2") (pin "2") (pinfunction "2_2") (pintype "passive"))
      (node (ref "OP1NEGGND") (pin "2") (pinfunction "2_2") (pintype "passive"))
      (node (ref "OP1POSGND") (pin "1") (pinfunction "1_1") (pintype "passive"))
      (node (ref "OP2NEGGND") (pin "2") (pinfunction "2_2") (pintype "passive"))
      (node (ref "OP2POSGND") (pin "2") (pinfunction "2_2") (pintype "passive"))
      (node (ref "OUTPUTS") (pin "2") (pinfunction "2_2") (pintype "passive"))
      (node (ref "POWER") (pin "2") (pinfunction "2_2") (pintype "passive"))
      (node (ref "R19") (pin "2") (pinfunction "2_2") (pintype "bidirectional"))
      (node (ref "R20") (pin "2") (pinfunction "2_2") (pintype "bidirectional"))
      (node (ref "R21") (pin "2") (pinfunction "2_2") (pintype "bidirectional"))
      (node (ref "R22") (pin "2") (pinfunction "2_2") (pintype "bidirectional"))
      (node (ref "U$1") (pin "1") (pinfunction "1_1") (pintype "passive"))
      (node (ref "U$1") (pin "10") (pinfunction "10_10") (pintype "passive"))
      (node (ref "U$1") (pin "11") (pinfunction "11_11") (pintype "passive"))
      (node (ref "U$1") (pin "12") (pinfunction "12_12") (pintype "passive"))
      (node (ref "U$1") (pin "13") (pinfunction "13_13") (pintype "passive"))
      (node (ref "U$1") (pin "14") (pinfunction "14_14") (pintype "passive"))
      (node (ref "U$1") (pin "15") (pinfunction "15_15") (pintype "passive"))
      (node (ref "U$1") (pin "16") (pinfunction "16_16") (pintype "passive"))
      (node (ref "U$1") (pin "17") (pinfunction "17_17") (pintype "passive"))
      (node (ref "U$1") (pin "18") (pinfunction "18_18") (pintype "passive"))
      (node (ref "U$1") (pin "19") (pinfunction "19_19") (pintype "passive"))
      (node (ref "U$1") (pin "2") (pinfunction "2_2") (pintype "passive"))
      (node (ref "U$1") (pin "20") (pinfunction "20_20") (pintype "passive"))
      (node (ref "U$1") (pin "21") (pinfunction "21_21") (pintype "passive"))
      (node (ref "U$1") (pin "22") (pinfunction "22_22") (pintype "passive"))
      (node (ref "U$1") (pin "23") (pinfunction "23_23") (pintype "passive"))
      (node (ref "U$1") (pin "24") (pinfunction "24_24") (pintype "passive"))
      (node (ref "U$1") (pin "25") (pinfunction "25_25") (pintype "passive"))
      (node (ref "U$1") (pin "26") (pinfunction "26_26") (pintype "passive"))
      (node (ref "U$1") (pin "27") (pinfunction "27_27") (pintype "passive"))
      (node (ref "U$1") (pin "28") (pinfunction "28_28") (pintype "passive"))
      (node (ref "U$1") (pin "29") (pinfunction "29_29") (pintype "passive"))
      (node (ref "U$1") (pin "3") (pinfunction "3_3") (pintype "passive"))
      (node (ref "U$1") (pin "30") (pinfunction "30_30") (pintype "passive"))
      (node (ref "U$1") (pin "31") (pinfunction "31_31") (pintype "passive"))
      (node (ref "U$1") (pin "32") (pinfunction "32_32") (pintype "passive"))
      (node (ref "U$1") (pin "33") (pinfunction "33_33") (pintype "passive"))
      (node (ref "U$1") (pin "34") (pinfunction "34_34") (pintype "passive"))
      (node (ref "U$1") (pin "35") (pinfunction "35_35") (pintype "passive"))
      (node (ref "U$1") (pin "36") (pinfunction "36_36") (pintype "passive"))
      (node (ref "U$1") (pin "37") (pinfunction "37_37") (pintype "passive"))
      (node (ref "U$1") (pin "38") (pinfunction "38_38") (pintype "passive"))
      (node (ref "U$1") (pin "39") (pinfunction "39_39") (pintype "passive"))
      (node (ref "U$1") (pin "4") (pinfunction "4_4") (pintype "passive"))
      (node (ref "U$1") (pin "40") (pinfunction "40_40") (pintype "passive"))
      (node (ref "U$1") (pin "5") (pinfunction "5_5") (pintype "passive"))
      (node (ref "U$1") (pin "6") (pinfunction "6_6") (pintype "passive"))
      (node (ref "U$1") (pin "7") (pinfunction "7_7") (pintype "passive"))
      (node (ref "U$1") (pin "8") (pinfunction "8_8") (pintype "passive"))
      (node (ref "U$1") (pin "9") (pinfunction "9_9") (pintype "passive"))
      (node (ref "U$12") (pin "11") (pinfunction "11_11") (pintype "passive"))
      (node (ref "U$12") (pin "15") (pinfunction "15_15") (pintype "passive"))
      (node (ref "U$12") (pin "16") (pinfunction "16_16") (pintype "passive"))
      (node (ref "U$12") (pin "19") (pinfunction "19_19") (pintype "passive"))
      (node (ref "U$12") (pin "23") (pinfunction "23_23") (pintype "passive"))
      (node (ref "U$12") (pin "24") (pinfunction "24_24") (pintype "passive"))
      (node (ref "U$12") (pin "27") (pinfunction "27_27") (pintype "passive"))
      (node (ref "U$12") (pin "3") (pinfunction "3_3") (pintype "passive"))
      (node (ref "U$12") (pin "31") (pinfunction "31_31") (pintype "passive"))
      (node (ref "U$12") (pin "32") (pinfunction "32_32") (pintype "passive"))
      (node (ref "U$12") (pin "35") (pinfunction "35_35") (pintype "passive"))
      (node (ref "U$12") (pin "39") (pinfunction "39_39") (pintype "passive"))
      (node (ref "U$12") (pin "40") (pinfunction "40_40") (pintype "passive"))
      (node (ref "U$12") (pin "7") (pinfunction "7_7") (pintype "passive"))
      (node (ref "U$12") (pin "8") (pinfunction "8_8") (pintype "passive"))
      (node (ref "U$9") (pin "3") (pinfunction "GND_3") (pintype "bidirectional"))
      (node (ref "U$9") (pin "4") (pinfunction "GND_4") (pintype "bidirectional"))
      (node (ref "U$9") (pin "5") (pinfunction "GND_5") (pintype "bidirectional"))
      (node (ref "U$9") (pin "6") (pinfunction "GND_6") (pintype "bidirectional"))
      (node (ref "U$9") (pin "7") (pinfunction "GND_7") (pintype "bidirectional"))
      (node (ref "U$9") (pin "8") (pinfunction "GND_8") (pintype "bidirectional"))
      (node (ref "U2") (pin "4") (pinfunction "GND_4") (pintype "bidirectional"))
    )
    (net (code "44") (name "Net-(C7-1)") (class "Default")
      (node (ref "C5") (pin "2") (pinfunction "2_2") (pintype "bidirectional"))
      (node (ref "C7") (pin "+") (pinfunction "1_+") (pintype "bidirectional"))
      (node (ref "IC1") (pin "8") (pinfunction "V+_8") (pintype "power_in"))
      (node (ref "OP1POSGND5") (pin "1") (pinfunction "1_1") (pintype "passive"))
      (node (ref "POWER") (pin "1") (pinfunction "1_1") (pintype "passive"))
    )
    (net (code "45") (name "Net-(C8-2)") (class "Default")
      (node (ref "C6") (pin "1") (pinfunction "1_1") (pintype "bidirectional"))
      (node (ref "C8") (pin "-") (pinfunction "2_-") (pintype "bidirectional"))
      (node (ref "IC1") (pin "4") (pinfunction "V-_4") (pintype "power_in"))
      (node (ref "OP1POSGND6") (pin "2") (pinfunction "2_2") (pintype "passive"))
      (node (ref "POWER") (pin "3") (pinfunction "3_3") (pintype "passive"))
    )
    (net (code "46") (name "Net-(D1-Pad+)") (class "Default")
      (node (ref "D1") (pin "+") (pinfunction "+_+") (pintype "passive"))
      (node (ref "R23") (pin "2") (pinfunction "2_2") (pintype "bidirectional"))
    )
    (net (code "47") (name "Net-(D2-Pad-)") (class "Default")
      (node (ref "D2") (pin "-") (pinfunction "-_-") (pintype "passive"))
      (node (ref "R24") (pin "1") (pinfunction "1_1") (pintype "bidirectional"))
    )
    (net (code "48") (name "Net-(D3-Pad+)") (class "Default")
      (node (ref "D3") (pin "+") (pinfunction "+_+") (pintype "passive"))
      (node (ref "R25") (pin "2") (pinfunction "2_2") (pintype "bidirectional"))
    )
    (net (code "49") (name "Net-(D4-PadA)") (class "Default")
      (node (ref "D4") (pin "A") (pinfunction "A_A") (pintype "passive"))
      (node (ref "U$9") (pin "10") (pinfunction "+12V_10") (pintype "bidirectional"))
      (node (ref "U$9") (pin "9") (pinfunction "+12V_9") (pintype "bidirectional"))
    )
    (net (code "50") (name "Net-(D5-PadC)") (class "Default")
      (node (ref "D5") (pin "C") (pinfunction "C_C") (pintype "passive"))
      (node (ref "U$9") (pin "1") (pinfunction "-12V_1") (pintype "bidirectional"))
      (node (ref "U$9") (pin "2") (pinfunction "-12V_2") (pintype "bidirectional"))
    )
    (net (code "51") (name "Net-(D6-PadA)") (class "Default")
      (node (ref "D6") (pin "A") (pinfunction "A_A") (pintype "passive"))
      (node (ref "U$9") (pin "11") (pinfunction "+5V_11") (pintype "bidirectional"))
      (node (ref "U$9") (pin "12") (pinfunction "+5V_12") (pintype "bidirectional"))
    )
    (net (code "52") (name "Net-(OP1NEG-Pad1)") (class "Default")
      (node (ref "OP1NEG") (pin "1") (pinfunction "1_1") (pintype "passive"))
      (node (ref "R12") (pin "2") (pinfunction "2_2") (pintype "bidirectional"))
    )
    (net (code "53") (name "Net-(OP1NEG-Pad2)") (class "Default")
      (node (ref "OP1NEG") (pin "2") (pinfunction "2_2") (pintype "passive"))
      (node (ref "R11") (pin "2") (pinfunction "2_2") (pintype "bidirectional"))
    )
    (net (code "54") (name "Net-(OP1NEG-Pad3)") (class "Default")
      (node (ref "OP1NEG") (pin "3") (pinfunction "3_3") (pintype "passive"))
      (node (ref "R10") (pin "2") (pinfunction "2_2") (pintype "bidirectional"))
    )
    (net (code "55") (name "Net-(OP1POS-Pad1)") (class "Default")
      (node (ref "OP1POS") (pin "1") (pinfunction "1_1") (pintype "passive"))
      (node (ref "R7") (pin "2") (pinfunction "2_2") (pintype "bidirectional"))
    )
    (net (code "56") (name "Net-(OP1POS-Pad2)") (class "Default")
      (node (ref "OP1POS") (pin "2") (pinfunction "2_2") (pintype "passive"))
      (node (ref "R8") (pin "2") (pinfunction "2_2") (pintype "bidirectional"))
    )
    (net (code "57") (name "Net-(OP1POS-Pad3)") (class "Default")
      (node (ref "OP1POS") (pin "3") (pinfunction "3_3") (pintype "passive"))
      (node (ref "R9") (pin "2") (pinfunction "2_2") (pintype "bidirectional"))
    )
    (net (code "58") (name "Net-(OP1TOOP2NEG-Pad1)") (class "Default")
      (node (ref "OP1TOOP2NEG") (pin "1") (pinfunction "1_1") (pintype "bidirectional"))
      (node (ref "OP1TOOP2POS") (pin "1") (pinfunction "1_1") (pintype "bidirectional"))
      (node (ref "OUTPUTS") (pin "1") (pinfunction "1_1") (pintype "passive"))
      (node (ref "R6") (pin "1") (pinfunction "1_1") (pintype "bidirectional"))
    )
    (net (code "59") (name "Net-(OP2NEG-Pad1)") (class "Default")
      (node (ref "OP2NEG") (pin "1") (pinfunction "1_1") (pintype "passive"))
      (node (ref "R18") (pin "1") (pinfunction "1_1") (pintype "bidirectional"))
    )
    (net (code "60") (name "Net-(OP2NEG-Pad2)") (class "Default")
      (node (ref "OP2NEG") (pin "2") (pinfunction "2_2") (pintype "passive"))
      (node (ref "R17") (pin "1") (pinfunction "1_1") (pintype "bidirectional"))
    )
    (net (code "61") (name "Net-(OP2NEG-Pad3)") (class "Default")
      (node (ref "OP2NEG") (pin "3") (pinfunction "3_3") (pintype "passive"))
      (node (ref "R16") (pin "1") (pinfunction "1_1") (pintype "bidirectional"))
    )
    (net (code "62") (name "Net-(OP2POS-Pad1)") (class "Default")
      (node (ref "OP2POS") (pin "1") (pinfunction "1_1") (pintype "passive"))
      (node (ref "R15") (pin "1") (pinfunction "1_1") (pintype "bidirectional"))
    )
    (net (code "63") (name "Net-(OP2POS-Pad2)") (class "Default")
      (node (ref "OP2POS") (pin "2") (pinfunction "2_2") (pintype "passive"))
      (node (ref "R14") (pin "1") (pinfunction "1_1") (pintype "bidirectional"))
    )
    (net (code "64") (name "Net-(OP2POS-Pad3)") (class "Default")
      (node (ref "OP2POS") (pin "3") (pinfunction "3_3") (pintype "passive"))
      (node (ref "R13") (pin "1") (pinfunction "1_1") (pintype "bidirectional"))
    )
    (net (code "65") (name "Net-(OP2TEST11-Pad1)") (class "Default")
      (node (ref "OP2TEST11") (pin "1") (pinfunction "1_1") (pintype "passive"))
      (node (ref "OP2TEST14") (pin "1") (pinfunction "1_1") (pintype "passive"))
      (node (ref "TM1") (pin "E") (pinfunction "E_E") (pintype "passive"))
    )
    (net (code "66") (name "Net-(OP2TEST11-Pad2)") (class "Default")
      (node (ref "OP2TEST11") (pin "2") (pinfunction "2_2") (pintype "passive"))
      (node (ref "OP2TEST14") (pin "2") (pinfunction "2_2") (pintype "passive"))
      (node (ref "TM1") (pin "S") (pinfunction "S_S") (pintype "passive"))
    )
    (net (code "67") (name "Net-(OP2TEST11-Pad3)") (class "Default")
      (node (ref "OP2TEST11") (pin "3") (pinfunction "3_3") (pintype "passive"))
      (node (ref "OP2TEST14") (pin "3") (pinfunction "3_3") (pintype "passive"))
      (node (ref "TM1") (pin "A") (pinfunction "A_A") (pintype "passive"))
    )
    (net (code "68") (name "Net-(OP2TEST12-Pad1)") (class "Default")
      (node (ref "OP2TEST12") (pin "1") (pinfunction "1_1") (pintype "passive"))
      (node (ref "OP2TEST13") (pin "1") (pinfunction "1_1") (pintype "passive"))
      (node (ref "TM2") (pin "E") (pinfunction "E_E") (pintype "passive"))
    )
    (net (code "69") (name "Net-(OP2TEST12-Pad2)") (class "Default")
      (node (ref "OP2TEST12") (pin "2") (pinfunction "2_2") (pintype "passive"))
      (node (ref "OP2TEST13") (pin "2") (pinfunction "2_2") (pintype "passive"))
      (node (ref "TM2") (pin "S") (pinfunction "S_S") (pintype "passive"))
    )
    (net (code "70") (name "Net-(OP2TEST12-Pad3)") (class "Default")
      (node (ref "OP2TEST12") (pin "3") (pinfunction "3_3") (pintype "passive"))
      (node (ref "OP2TEST13") (pin "3") (pinfunction "3_3") (pintype "passive"))
      (node (ref "TM2") (pin "A") (pinfunction "A_A") (pintype "passive"))
    )
    (net (code "71") (name "Net-(OP2TEST15-Pad1)") (class "Default")
      (node (ref "OP2TEST15") (pin "1") (pinfunction "1_1") (pintype "passive"))
      (node (ref "OP2TEST18") (pin "1") (pinfunction "1_1") (pintype "passive"))
      (node (ref "TM3") (pin "E") (pinfunction "E_E") (pintype "passive"))
    )
    (net (code "72") (name "Net-(OP2TEST15-Pad2)") (class "Default")
      (node (ref "OP2TEST15") (pin "2") (pinfunction "2_2") (pintype "passive"))
      (node (ref "OP2TEST18") (pin "2") (pinfunction "2_2") (pintype "passive"))
      (node (ref "TM3") (pin "S") (pinfunction "S_S") (pintype "passive"))
    )
    (net (code "73") (name "Net-(OP2TEST15-Pad3)") (class "Default")
      (node (ref "OP2TEST15") (pin "3") (pinfunction "3_3") (pintype "passive"))
      (node (ref "OP2TEST18") (pin "3") (pinfunction "3_3") (pintype "passive"))
      (node (ref "TM3") (pin "A") (pinfunction "A_A") (pintype "passive"))
    )
    (net (code "74") (name "Net-(OP2TEST16-Pad1)") (class "Default")
      (node (ref "OP2TEST16") (pin "1") (pinfunction "1_1") (pintype "passive"))
      (node (ref "OP2TEST17") (pin "1") (pinfunction "1_1") (pintype "passive"))
      (node (ref "TM4") (pin "E") (pinfunction "E_E") (pintype "passive"))
    )
    (net (code "75") (name "Net-(OP2TEST16-Pad2)") (class "Default")
      (node (ref "OP2TEST16") (pin "2") (pinfunction "2_2") (pintype "passive"))
      (node (ref "OP2TEST17") (pin "2") (pinfunction "2_2") (pintype "passive"))
      (node (ref "TM4") (pin "S") (pinfunction "S_S") (pintype "passive"))
    )
    (net (code "76") (name "Net-(OP2TEST16-Pad3)") (class "Default")
      (node (ref "OP2TEST16") (pin "3") (pinfunction "3_3") (pintype "passive"))
      (node (ref "OP2TEST17") (pin "3") (pinfunction "3_3") (pintype "passive"))
      (node (ref "TM4") (pin "A") (pinfunction "A_A") (pintype "passive"))
    )
    (net (code "77") (name "Net-(OUTPUTS-Pad3)") (class "Default")
      (node (ref "OUTPUTS") (pin "3") (pinfunction "3_3") (pintype "passive"))
      (node (ref "R5") (pin "1") (pinfunction "1_1") (pintype "bidirectional"))
    )
    (net (code "78") (name "unconnected-(U$32-P$1-PadG30)") (class "Default")
      (node (ref "U$32") (pin "G30") (pinfunction "P$1_G30") (pintype "bidirectional"))
    )
    (net (code "79") (name "unconnected-(U$32-P$2-PadG40)") (class "Default")
      (node (ref "U$32") (pin "G40") (pinfunction "P$2_G40") (pintype "bidirectional"))
    )
    (net (code "80") (name "unconnected-(U$32-P$3-PadV30)") (class "Default")
      (node (ref "U$32") (pin "V30") (pinfunction "P$3_V30") (pintype "bidirectional"))
    )
    (net (code "81") (name "unconnected-(U$32-P$4-PadV40)") (class "Default")
      (node (ref "U$32") (pin "V40") (pinfunction "P$4_V40") (pintype "bidirectional"))
    )
  )
)
